# CTRL_V5.net
KiCad netlist of a schematic drawn in Altium Designer
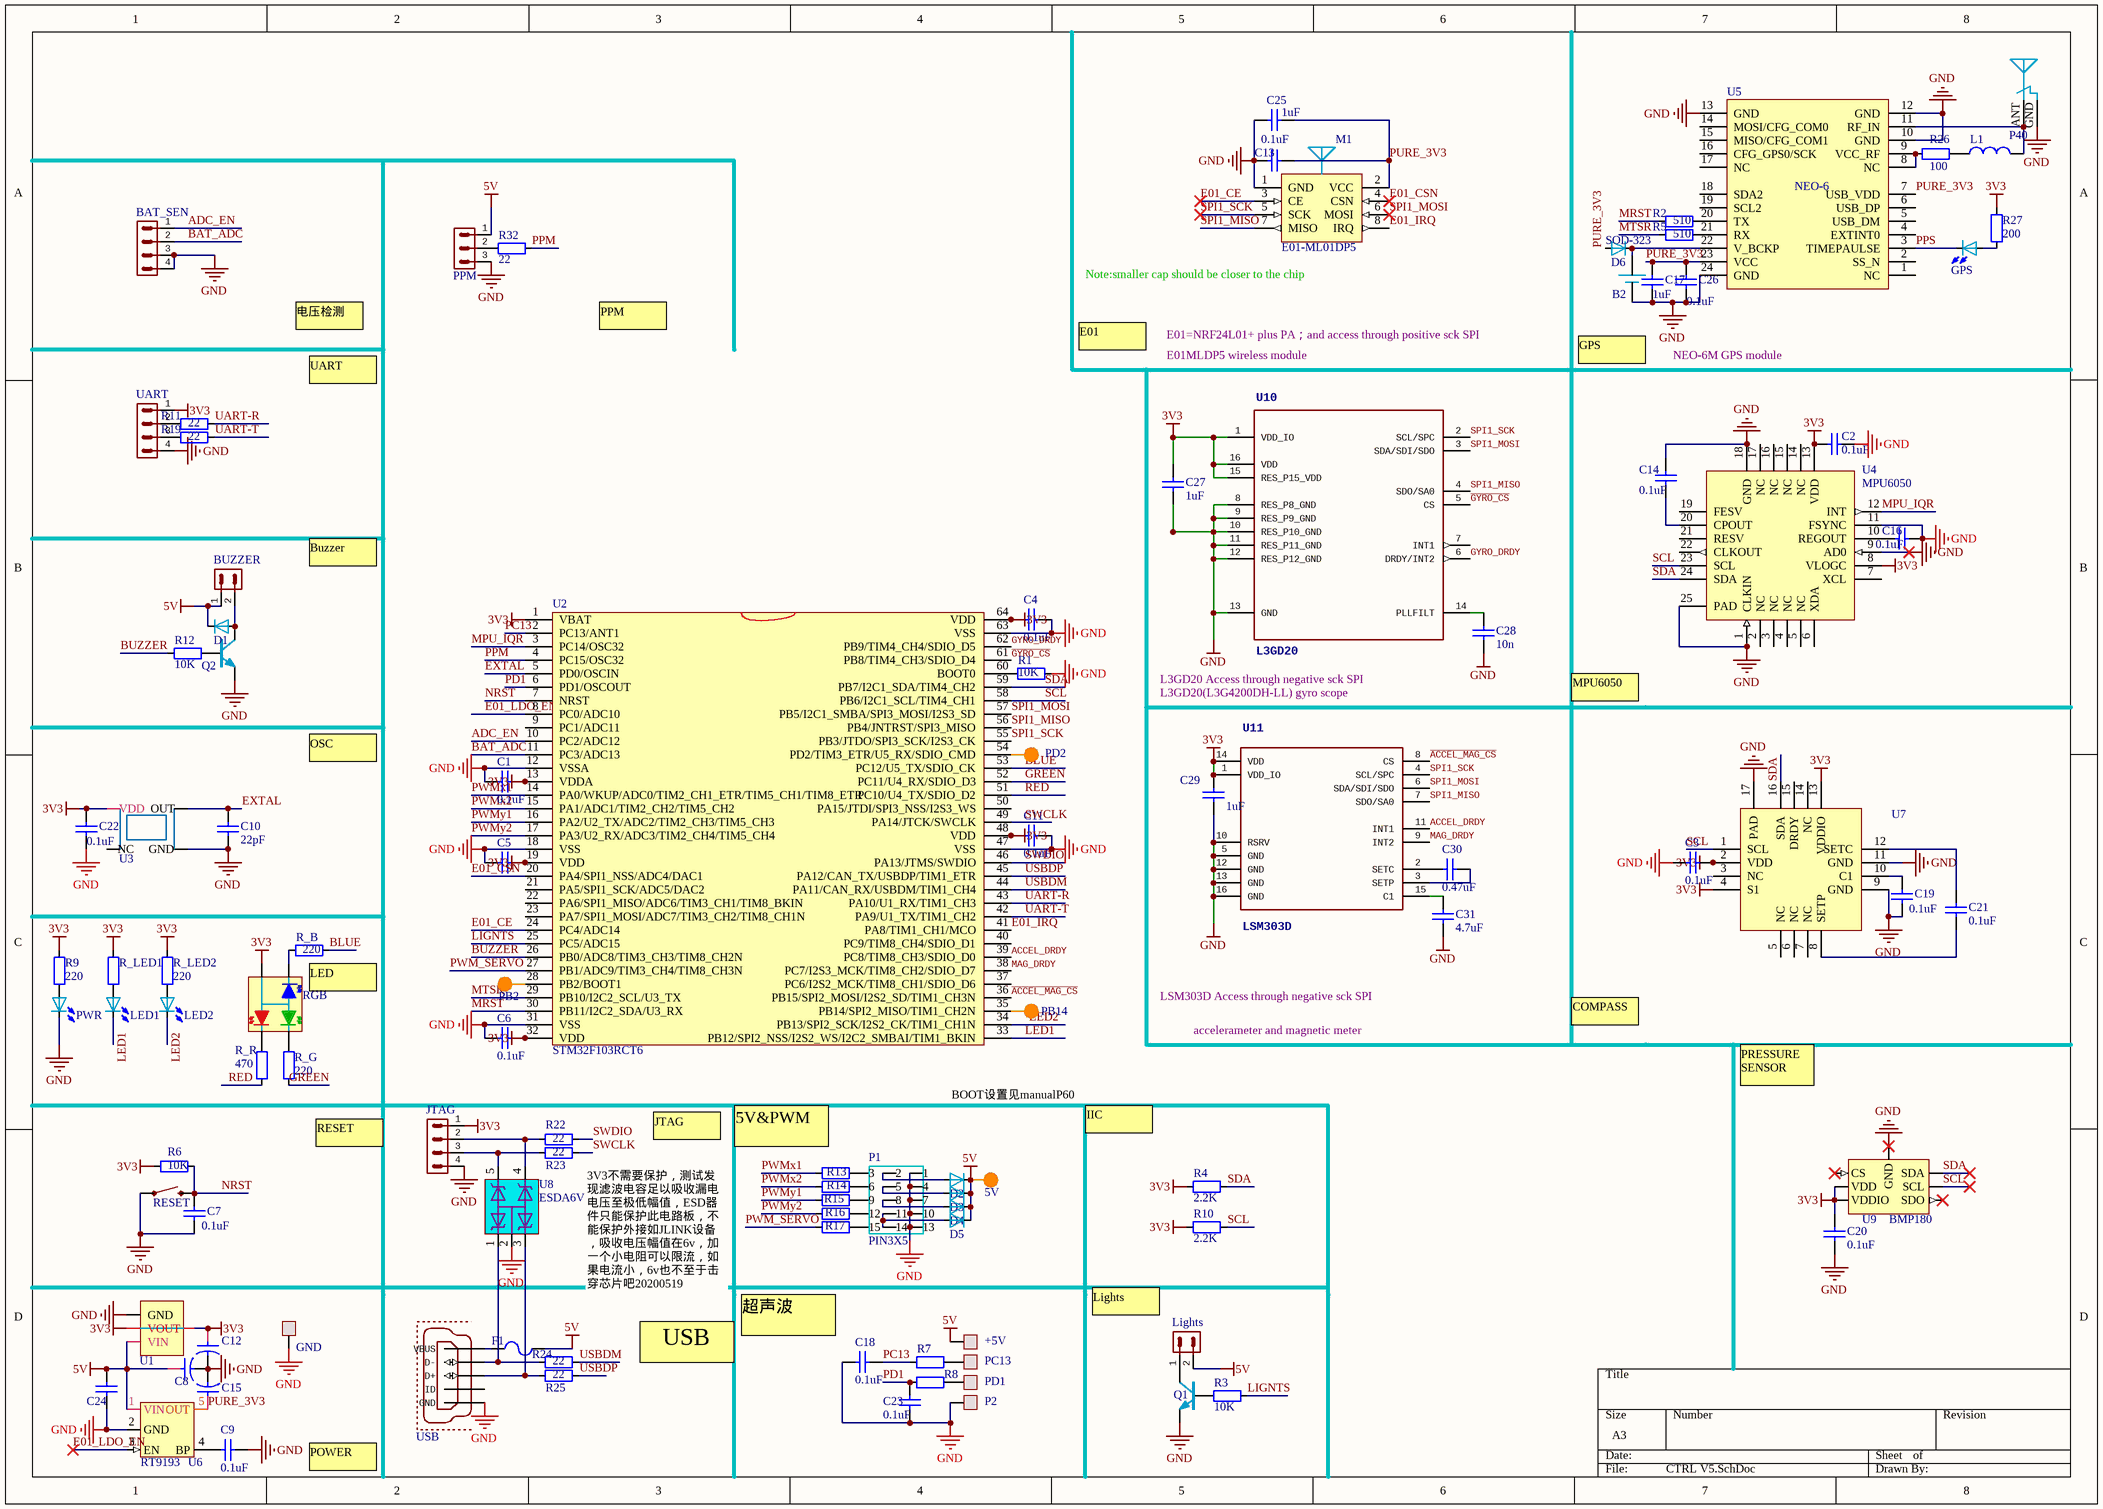
[diagram p0: CTRL V5.SchDoc]

(export (version "E")
  (design (tool "Eeschema 10.0.6"))
  (components
    (comp (ref "+5V") (value "voltage") (footprint "PIN1*1") (libsource (lib "") (part "PIN HDR 1x1_1")))
    (comp (ref "5V")
      (value "voltage")
      (footprint "TEST_P")
      (description "信号测试点")
      (libsource (lib "My_Library") (part "TEST"))
    )
    (comp (ref "B2")
      (value "XH414")
      (footprint "XH414")
      (description "XH414贴片法拉电容φ4.7")
      (libsource (lib "My_Library") (part "XH414"))
    )
    (comp (ref "BAT_SEN")
      (value "DF13C-4P")
      (footprint "DF13C-4P-1.25V")
      (description "1x4-Pin-connector")
      (fields (field (name "PUBLISHER") "Altium Limited"))
      (libsource (lib "My_Library") (part "PIN HDR 1x4"))
    )
    (comp (ref "BUZZER")
      (value "DF13C-2P")
      (footprint "DF13C-2P-1.25V")
      (description "DF13C-2PHeader, 2-Pin")
      (fields (field (name "PUBLISHER") "Altium Limited"))
      (libsource (lib "My_Library") (part "PIN HDR 1x2"))
    )
    (comp (ref "C1")
      (value "0.1uF")
      (footprint "0603-CAP")
      (description "无极性Cap")
      (fields (field (name "VOLTAGE") "50V") (field (name "PUBLISHER") "Altium Limited"))
      (libsource (lib "My_Library") (part "Cap"))
    )
    (comp (ref "C2")
      (value "0.1uF")
      (footprint "0603-CAP")
      (description "无极性Cap")
      (fields (field (name "VOLTAGE") "50V") (field (name "PUBLISHER") "Altium Limited"))
      (libsource (lib "My_Library") (part "Cap"))
    )
    (comp (ref "C3")
      (value "0.1uF")
      (footprint "0603-CAP")
      (description "无极性Cap")
      (fields (field (name "VOLTAGE") "50V") (field (name "PUBLISHER") "Altium Limited"))
      (libsource (lib "My_Library") (part "Cap"))
    )
    (comp (ref "C4")
      (value "0.1uF")
      (footprint "0603-CAP")
      (description "无极性Cap")
      (fields (field (name "VOLTAGE") "50V") (field (name "PUBLISHER") "Altium Limited"))
      (libsource (lib "My_Library") (part "Cap"))
    )
    (comp (ref "C5")
      (value "0.1uF")
      (footprint "0603-CAP")
      (description "无极性Cap")
      (fields (field (name "VOLTAGE") "50V") (field (name "PUBLISHER") "Altium Limited"))
      (libsource (lib "My_Library") (part "Cap"))
    )
    (comp (ref "C6")
      (value "0.1uF")
      (footprint "0603-CAP")
      (description "无极性Cap")
      (fields (field (name "VOLTAGE") "50V") (field (name "PUBLISHER") "Altium Limited"))
      (libsource (lib "My_Library") (part "Cap"))
    )
    (comp (ref "C7")
      (value "0.1uF")
      (footprint "0603-CAP")
      (description "无极性Cap")
      (fields (field (name "VOLTAGE") "50V") (field (name "PUBLISHER") "Altium Limited"))
      (libsource (lib "My_Library") (part "Cap"))
    )
    (comp (ref "C8")
      (value "10uF")
      (footprint "TAJ-A(1206)[3216]")
      (description "有极性Cap")
      (libsource (lib "") (part "Cap_p_1"))
    )
    (comp (ref "C9")
      (value "0.1uF")
      (footprint "0603-CAP")
      (description "无极性Cap")
      (fields (field (name "VOLTAGE") "50V") (field (name "PUBLISHER") "Altium Limited"))
      (libsource (lib "My_Library") (part "Cap"))
    )
    (comp (ref "C10")
      (value "22pF")
      (footprint "0603-CAP")
      (description "无极性Cap")
      (fields (field (name "VOLTAGE") "50V") (field (name "PUBLISHER") "Altium Limited"))
      (libsource (lib "My_Library") (part "Cap"))
    )
    (comp (ref "C11")
      (value "0.1uF")
      (footprint "0603-CAP")
      (description "无极性Cap")
      (fields (field (name "VOLTAGE") "50V") (field (name "PUBLISHER") "Altium Limited"))
      (libsource (lib "My_Library") (part "Cap"))
    )
    (comp (ref "C12")
      (value "10uF")
      (footprint "TAJ-A(1206)[3216]")
      (description "有极性Cap")
      (libsource (lib "My_Library") (part "Cap_p"))
    )
    (comp (ref "C13")
      (value "0.1uF")
      (footprint "0603-CAP")
      (description "无极性Cap")
      (fields (field (name "VOLTAGE") "50V") (field (name "PUBLISHER") "Altium Limited"))
      (libsource (lib "My_Library") (part "Cap"))
    )
    (comp (ref "C14")
      (value "0.1uF")
      (footprint "0603-CAP")
      (description "无极性Cap")
      (fields (field (name "VOLTAGE") "50V") (field (name "PUBLISHER") "Altium Limited"))
      (libsource (lib "My_Library") (part "Cap"))
    )
    (comp (ref "C15")
      (value "10uF")
      (footprint "TAJ-A(1206)[3216]")
      (description "有极性Cap")
      (libsource (lib "My_Library") (part "Cap_p"))
    )
    (comp (ref "C16")
      (value "0.1uF")
      (footprint "0603-CAP")
      (description "无极性Cap")
      (fields (field (name "VOLTAGE") "50V") (field (name "PUBLISHER") "Altium Limited"))
      (libsource (lib "My_Library") (part "Cap"))
    )
    (comp (ref "C17")
      (value "1uF")
      (footprint "0805-CAP")
      (description "无极性Cap")
      (fields (field (name "VOLTAGE") "50V") (field (name "PUBLISHER") "Altium Limited"))
      (libsource (lib "My_Library") (part "Cap"))
    )
    (comp (ref "C18")
      (value "0.1uF")
      (footprint "0603-CAP")
      (description "无极性Cap")
      (fields (field (name "VOLTAGE") "50V") (field (name "PUBLISHER") "Altium Limited"))
      (libsource (lib "My_Library") (part "Cap"))
    )
    (comp (ref "C19")
      (value "0.1uF")
      (footprint "0603-CAP")
      (description "无极性Cap")
      (fields (field (name "VOLTAGE") "50V") (field (name "PUBLISHER") "Altium Limited"))
      (libsource (lib "My_Library") (part "Cap"))
    )
    (comp (ref "C20")
      (value "0.1uF")
      (footprint "0603-CAP")
      (description "无极性Cap")
      (fields (field (name "VOLTAGE") "50V") (field (name "PUBLISHER") "Altium Limited"))
      (libsource (lib "My_Library") (part "Cap"))
    )
    (comp (ref "C21")
      (value "0.1uF")
      (footprint "0603-CAP")
      (description "无极性Cap")
      (fields (field (name "VOLTAGE") "50V") (field (name "PUBLISHER") "Altium Limited"))
      (libsource (lib "My_Library") (part "Cap"))
    )
    (comp (ref "C22")
      (value "0.1uF")
      (footprint "0603-CAP")
      (description "无极性Cap")
      (fields (field (name "VOLTAGE") "50V") (field (name "PUBLISHER") "Altium Limited"))
      (libsource (lib "My_Library") (part "Cap"))
    )
    (comp (ref "C23")
      (value "0.1uF")
      (footprint "0603-CAP")
      (description "无极性Cap")
      (fields (field (name "VOLTAGE") "50V") (field (name "PUBLISHER") "Altium Limited"))
      (libsource (lib "My_Library") (part "Cap"))
    )
    (comp (ref "C24")
      (value "0.1uF")
      (footprint "0805-CAP")
      (description "无极性Cap")
      (fields (field (name "VOLTAGE") "50V") (field (name "PUBLISHER") "Altium Limited"))
      (libsource (lib "My_Library") (part "Cap"))
    )
    (comp (ref "C25")
      (value "1uF")
      (footprint "0805-CAP")
      (description "无极性Cap")
      (fields (field (name "VOLTAGE") "50V") (field (name "PUBLISHER") "Altium Limited"))
      (libsource (lib "My_Library") (part "Cap"))
    )
    (comp (ref "C26")
      (value "0.1uF")
      (footprint "0603-CAP")
      (description "无极性Cap")
      (fields (field (name "VOLTAGE") "50V") (field (name "PUBLISHER") "Altium Limited"))
      (libsource (lib "My_Library") (part "Cap"))
    )
    (comp (ref "C27")
      (value "1uF")
      (footprint "0805-CAP")
      (description "无极性Cap")
      (fields (field (name "VOLTAGE") "50V") (field (name "PUBLISHER") "Altium Limited"))
      (libsource (lib "My_Library") (part "Cap"))
    )
    (comp (ref "C28")
      (value "10n")
      (footprint "0603-CAP")
      (description "无极性Cap")
      (fields (field (name "VOLTAGE") "50V") (field (name "PUBLISHER") "Altium Limited"))
      (libsource (lib "My_Library") (part "Cap"))
    )
    (comp (ref "C29")
      (value "1uF")
      (footprint "0805-CAP")
      (description "无极性Cap")
      (fields (field (name "VOLTAGE") "50V") (field (name "PUBLISHER") "Altium Limited"))
      (libsource (lib "My_Library") (part "Cap"))
    )
    (comp (ref "C30")
      (value "0.47uF")
      (footprint "0603-CAP")
      (description "无极性Cap")
      (fields (field (name "VOLTAGE") "50V") (field (name "PUBLISHER") "Altium Limited"))
      (libsource (lib "My_Library") (part "Cap"))
    )
    (comp (ref "C31")
      (value "4.7uF")
      (footprint "0805-CAP")
      (description "无极性Cap")
      (fields (field (name "VOLTAGE") "50V") (field (name "PUBLISHER") "Altium Limited"))
      (libsource (lib "My_Library") (part "Cap"))
    )
    (comp (ref "D1")
      (value "shotechy")
      (footprint "SOD-323")
      (description "Diode")
      (libsource (lib "My_Library") (part "DIODE"))
    )
    (comp (ref "D2")
      (value "1N4148")
      (footprint "SOD-523")
      (description "Diode")
      (libsource (lib "My_Library") (part "DIODE"))
    )
    (comp (ref "D3")
      (value "1N4148")
      (footprint "SOD-523")
      (description "Diode")
      (libsource (lib "My_Library") (part "DIODE"))
    )
    (comp (ref "D4")
      (value "1N4148")
      (footprint "SOD-523")
      (description "Diode")
      (libsource (lib "My_Library") (part "DIODE"))
    )
    (comp (ref "D5")
      (value "1N4148")
      (footprint "SOD-523")
      (description "Diode")
      (libsource (lib "My_Library") (part "DIODE"))
    )
    (comp (ref "D6")
      (value "SOD-323")
      (footprint "SOD-323")
      (description "Diode")
      (libsource (lib "My_Library") (part "DIODE"))
    )
    (comp (ref "F1")
      (value "FUSE")
      (footprint "0805-FUS")
      (description "熔断器")
      (libsource (lib "My_Library") (part "FUSE"))
    )
    (comp (ref "GND")
      (value "voltage")
      (footprint "PIN1*1")
      (libsource (lib "My_Library") (part "PIN HDR 1x1"))
    )
    (comp (ref "GPS") (value "LED") (footprint "0805-LED") (libsource (lib "My_Library") (part "LED")))
    (comp (ref "JTAG")
      (value "PIN HDR 1x4")
      (footprint "PIN4*1")
      (description "1x4-Pin-connector-JTAG")
      (fields (field (name "PUBLISHER") "Altium Limited"))
      (libsource (lib "My_Library") (part "PIN HDR 1x4"))
    )
    (comp (ref "L1")
      (value "value")
      (footprint "0805-IND")
      (description "电感")
      (libsource (lib "My_Library") (part "Inductor"))
    )
    (comp (ref "LED1") (value "LED") (footprint "0805-LED") (libsource (lib "My_Library") (part "LED")))
    (comp (ref "LED2") (value "LED") (footprint "0805-LED") (libsource (lib "My_Library") (part "LED")))
    (comp (ref "Lights")
      (value "DF13C-2P")
      (footprint "DF13C-2P-1.25V")
      (description "Header, 2-Pin")
      (fields (field (name "PUBLISHER") "Altium Limited"))
      (libsource (lib "My_Library") (part "PIN HDR 1x2"))
    )
    (comp (ref "M1")
      (value "E01-ML01DP5")
      (footprint "E01-ML01DP5 - SMD")
      (description "无线模块E01-ML01DP5")
      (libsource (lib "My_Library") (part "E01-ML01DP5"))
    )
    (comp (ref "P1")
      (value "PIN3X5")
      (footprint "PIN HDR3X5")
      (libsource (lib "My_Library") (part "PIN HDR3x5"))
    )
    (comp (ref "P2") (value "voltage") (footprint "PIN1*1") (libsource (lib "") (part "PIN HDR 1x1_1")))
    (comp (ref "P40")
      (value "IPEX")
      (footprint "IPEX")
      (description "IPEX天线座")
      (libsource (lib "My_Library") (part "IPEX"))
    )
    (comp (ref "PB2")
      (value "voltage")
      (footprint "TEST_P")
      (description "信号测试点")
      (libsource (lib "My_Library") (part "TEST"))
    )
    (comp (ref "PB14")
      (value "voltage")
      (footprint "TEST_P")
      (description "信号测试点")
      (libsource (lib "My_Library") (part "TEST"))
    )
    (comp (ref "PC13") (value "voltage") (footprint "PIN1*1") (libsource (lib "") (part "PIN HDR 1x1_1")))
    (comp (ref "PD1") (value "voltage") (footprint "PIN1*1") (libsource (lib "") (part "PIN HDR 1x1_1")))
    (comp (ref "PD2")
      (value "voltage")
      (footprint "TEST_P")
      (description "信号测试点")
      (libsource (lib "My_Library") (part "TEST"))
    )
    (comp (ref "PPM")
      (value "PIN HDR 1X3")
      (footprint "PIN3*1")
      (libsource (lib "My_Library") (part "PIN HDR 1X3"))
    )
    (comp (ref "PWR") (value "LED") (footprint "0805-LED") (libsource (lib "My_Library") (part "LED")))
    (comp (ref "Q1")
      (value "2N3904")
      (footprint "SOT-23")
      (description "NPN三极管")
      (libsource (lib "") (part "NPN_1"))
    )
    (comp (ref "Q2")
      (value "2N3904")
      (footprint "SOT-23")
      (description "NPN三极管")
      (libsource (lib "My_Library") (part "NPN"))
    )
    (comp (ref "R1")
      (value "10K")
      (footprint "0603-Res")
      (description "Resistor")
      (fields (field (name "PUBLISHER") "Altium Limited"))
      (libsource (lib "My_Library") (part "RES"))
    )
    (comp (ref "R2")
      (value "510")
      (footprint "0603-Res")
      (description "Resistor")
      (fields (field (name "PUBLISHER") "Altium Limited"))
      (libsource (lib "") (part "RES_1"))
    )
    (comp (ref "R3")
      (value "10K")
      (footprint "0603-Res")
      (description "Resistor")
      (fields (field (name "PUBLISHER") "Altium Limited"))
      (libsource (lib "") (part "RES_2"))
    )
    (comp (ref "R4")
      (value "2.2K")
      (footprint "0603-Res")
      (description "Resistor")
      (fields (field (name "PUBLISHER") "Altium Limited"))
      (libsource (lib "My_Library") (part "RES"))
    )
    (comp (ref "R5")
      (value "510")
      (footprint "0603-Res")
      (description "Resistor")
      (fields (field (name "PUBLISHER") "Altium Limited"))
      (libsource (lib "") (part "RES_1"))
    )
    (comp (ref "R6")
      (value "10K")
      (footprint "0603-Res")
      (description "Resistor")
      (fields (field (name "PUBLISHER") "Altium Limited"))
      (libsource (lib "") (part "RES_1"))
    )
    (comp (ref "R7")
      (value "220")
      (footprint "0603-Res")
      (description "Resistor")
      (fields (field (name "PUBLISHER") "Altium Limited"))
      (libsource (lib "") (part "RES_1"))
    )
    (comp (ref "R8")
      (value "220")
      (footprint "0603-Res")
      (description "Resistor")
      (fields (field (name "PUBLISHER") "Altium Limited"))
      (libsource (lib "") (part "RES_1"))
    )
    (comp (ref "R9")
      (value "220")
      (footprint "0603-Res")
      (description "Resistor")
      (fields (field (name "PUBLISHER") "Altium Limited"))
      (libsource (lib "My_Library") (part "RES"))
    )
    (comp (ref "R10")
      (value "2.2K")
      (footprint "0603-Res")
      (description "Resistor")
      (fields (field (name "PUBLISHER") "Altium Limited"))
      (libsource (lib "My_Library") (part "RES"))
    )
    (comp (ref "R11")
      (value "22")
      (footprint "0603-Res")
      (description "Resistor")
      (fields (field (name "PUBLISHER") "Altium Limited"))
      (libsource (lib "") (part "RES_3"))
    )
    (comp (ref "R12")
      (value "10K")
      (footprint "0603-Res")
      (description "Resistor")
      (fields (field (name "PUBLISHER") "Altium Limited"))
      (libsource (lib "My_Library") (part "RES"))
    )
    (comp (ref "R13")
      (value "220")
      (footprint "0603-Res")
      (description "Resistor")
      (fields (field (name "PUBLISHER") "Altium Limited"))
      (libsource (lib "My_Library") (part "RES"))
    )
    (comp (ref "R14")
      (value "220")
      (footprint "0603-Res")
      (description "Resistor")
      (fields (field (name "PUBLISHER") "Altium Limited"))
      (libsource (lib "My_Library") (part "RES"))
    )
    (comp (ref "R15")
      (value "220")
      (footprint "0603-Res")
      (description "Resistor")
      (fields (field (name "PUBLISHER") "Altium Limited"))
      (libsource (lib "My_Library") (part "RES"))
    )
    (comp (ref "R16")
      (value "220")
      (footprint "0603-Res")
      (description "Resistor")
      (fields (field (name "PUBLISHER") "Altium Limited"))
      (libsource (lib "My_Library") (part "RES"))
    )
    (comp (ref "R17")
      (value "220")
      (footprint "0603-Res")
      (description "Resistor")
      (fields (field (name "PUBLISHER") "Altium Limited"))
      (libsource (lib "My_Library") (part "RES"))
    )
    (comp (ref "R19")
      (value "22")
      (footprint "0603-Res")
      (description "Resistor")
      (fields (field (name "PUBLISHER") "Altium Limited"))
      (libsource (lib "") (part "RES_3"))
    )
    (comp (ref "R22")
      (value "22")
      (footprint "0603-Res")
      (description "Resistor")
      (fields (field (name "PUBLISHER") "Altium Limited"))
      (libsource (lib "") (part "RES_3"))
    )
    (comp (ref "R23")
      (value "22")
      (footprint "0603-Res")
      (description "Resistor")
      (fields (field (name "PUBLISHER") "Altium Limited"))
      (libsource (lib "") (part "RES_3"))
    )
    (comp (ref "R24")
      (value "22")
      (footprint "0603-Res")
      (description "Resistor")
      (fields (field (name "PUBLISHER") "Altium Limited"))
      (libsource (lib "") (part "RES_1"))
    )
    (comp (ref "R25")
      (value "22")
      (footprint "0603-Res")
      (description "Resistor")
      (fields (field (name "PUBLISHER") "Altium Limited"))
      (libsource (lib "") (part "RES_1"))
    )
    (comp (ref "R26")
      (value "100")
      (footprint "0603-Res")
      (description "Resistor")
      (fields (field (name "PUBLISHER") "Altium Limited"))
      (libsource (lib "") (part "RES_1"))
    )
    (comp (ref "R27")
      (value "200")
      (footprint "0603-Res")
      (description "Resistor")
      (fields (field (name "PUBLISHER") "Altium Limited"))
      (libsource (lib "") (part "RES_3"))
    )
    (comp (ref "R32")
      (value "22")
      (footprint "0603-Res")
      (description "Resistor")
      (fields (field (name "PUBLISHER") "Altium Limited"))
      (libsource (lib "") (part "RES_2"))
    )
    (comp (ref "RESET")
      (value "KEY_2PIN")
      (footprint "KEY-SMD-2P-1")
      (libsource (lib "My_Library") (part "KEY_2PIN"))
    )
    (comp (ref "RGB")
      (value "3528LED")
      (footprint "1210-RGBLED")
      (libsource (lib "My_Library") (part "LED-RGB-4PIN"))
    )
    (comp (ref "R_B")
      (value "220")
      (footprint "0603-Res")
      (description "Resistor")
      (fields (field (name "PUBLISHER") "Altium Limited"))
      (libsource (lib "") (part "RES_3"))
    )
    (comp (ref "R_G")
      (value "220")
      (footprint "0603-Res")
      (description "Resistor")
      (fields (field (name "PUBLISHER") "Altium Limited"))
      (libsource (lib "My_Library") (part "RES"))
    )
    (comp (ref "R_LED1")
      (value "220")
      (footprint "0603-Res")
      (description "Resistor")
      (fields (field (name "PUBLISHER") "Altium Limited"))
      (libsource (lib "My_Library") (part "RES"))
    )
    (comp (ref "R_LED2")
      (value "220")
      (footprint "0603-Res")
      (description "Resistor")
      (fields (field (name "PUBLISHER") "Altium Limited"))
      (libsource (lib "My_Library") (part "RES"))
    )
    (comp (ref "R_R")
      (value "470")
      (footprint "0603-Res")
      (description "Resistor")
      (fields (field (name "PUBLISHER") "Altium Limited"))
      (libsource (lib "My_Library") (part "RES"))
    )
    (comp (ref "U1")
      (value "AMS1117-3.3")
      (footprint "SOT-223")
      (libsource (lib "My_Library") (part "AMS1117"))
    )
    (comp (ref "U2")
      (value "STM32F103RCT6")
      (footprint "LQFP-64-S")
      (libsource (lib "My_Library") (part "STM32F103RCT6"))
    )
    (comp (ref "U3")
      (value "5032-8M")
      (footprint "XTAL-5032-4P")
      (description "4PIN-5032晶振")
      (libsource (lib "My_Library") (part "XTAL-5032-4P"))
    )
    (comp (ref "U4")
      (value "MPU6050")
      (footprint "QFN-24")
      (description "dscrps三轴陀螺仪加速度计")
      (libsource (lib "My_Library") (part "MPU6050"))
    )
    (comp (ref "U5")
      (value "NEO-6")
      (footprint "NEO-6")
      (description "GPS")
      (libsource (lib "My_Library") (part "NEO-6"))
    )
    (comp (ref "U6") (value "RT9193") (footprint "SOT23-5") (libsource (lib "My_Library") (part "RT9193")))
    (comp (ref "U7")
      (value "HMC5883")
      (footprint "QFN-16-L")
      (description "地磁计")
      (libsource (lib "My_Library") (part "HMC5883"))
    )
    (comp (ref "U8")
      (value "ESDA6V1W5(Eb1)")
      (footprint "SOT323-5L")
      (description "ESD protection")
      (libsource (lib "My_Library") (part "ESDA6V1W5(Eb1)"))
    )
    (comp (ref "U9")
      (value "BMP180")
      (footprint "BMP180-WITHSHELL")
      (description "Special BOSCH pressure sensor")
      (libsource (lib "My_Library") (part "BMP180"))
    )
    (comp (ref "U10")
      (value "L3GD20")
      (footprint "L3G4200DH-MAN")
      (libsource (lib "pixhawk2") (part "L3G4200DH-LL"))
    )
    (comp (ref "U11") (value "LSM303D") (footprint "LGA-16L") (libsource (lib "pixhawk2") (part "LSM303D")))
    (comp (ref "UART")
      (value "SH1.0-4P")
      (footprint "SH1.0 S-W-4P")
      (description "SH1.0-4P 1x4-Pin-connector")
      (fields (field (name "PUBLISHER") "Altium Limited"))
      (libsource (lib "My_Library") (part "PIN HDR 1x4"))
    )
    (comp (ref "USB")
      (value "USB-MICRO")
      (footprint "USB_MICRO")
      (description "USB")
      (libsource (lib "My_Library") (part "USB"))
    )
  )
  (nets
    (net (code "1") (name "/ACCEL_DRDY") (class "Default")
      (node (ref "U11") (pin "11") (pinfunction "INT1_11") (pintype "passive"))
      (node (ref "U2") (pin "39") (pinfunction "PC8/TIM8_CH3/SDIO_D0_39") (pintype "passive"))
    )
    (net (code "2") (name "/ADC_EN") (class "Default")
      (node (ref "BAT_SEN") (pin "1") (pinfunction "1_1") (pintype "passive"))
      (node (ref "U2") (pin "10") (pinfunction "PC2/ADC12_10") (pintype "passive"))
    )
    (net (code "3") (name "/BAT_ADC") (class "Default")
      (node (ref "BAT_SEN") (pin "2") (pinfunction "2_2") (pintype "passive"))
      (node (ref "U2") (pin "11") (pinfunction "PC3/ADC13_11") (pintype "passive"))
    )
    (net (code "4") (name "/BLUE") (class "Default")
      (node (ref "R_B") (pin "2") (pinfunction "2_2") (pintype "passive"))
      (node (ref "U2") (pin "53") (pinfunction "PC12/U5_TX/SDIO_CK_53") (pintype "passive"))
    )
    (net (code "5") (name "/BUZZER") (class "Default")
      (node (ref "R12") (pin "2") (pinfunction "2_2") (pintype "passive"))
      (node (ref "U2") (pin "26") (pinfunction "PB0/ADC8/TIM3_CH3/TIM8_CH2N_26") (pintype "passive"))
    )
    (net (code "6") (name "/E01_CE") (class "Default")
      (node (ref "M1") (pin "3") (pinfunction "CE_3") (pintype "input"))
      (node (ref "U2") (pin "24") (pinfunction "PC4/ADC14_24") (pintype "passive"))
    )
    (net (code "7") (name "/E01_CSN") (class "Default")
      (node (ref "M1") (pin "4") (pinfunction "CSN_4") (pintype "input"))
      (node (ref "U2") (pin "20") (pinfunction "PA4/SPI1_NSS/ADC4/DAC1_20") (pintype "passive"))
    )
    (net (code "8") (name "/E01_IRQ") (class "Default")
      (node (ref "M1") (pin "8") (pinfunction "IRQ_8") (pintype "output"))
      (node (ref "U2") (pin "41") (pinfunction "PA8/TIM1_CH1/MCO_41") (pintype "passive"))
    )
    (net (code "9") (name "/E01_LDO_EN") (class "Default")
      (node (ref "U2") (pin "8") (pinfunction "PC0/ADC10_8") (pintype "passive"))
      (node (ref "U6") (pin "3") (pinfunction "EN_3") (pintype "input"))
    )
    (net (code "10") (name "/EXTAL") (class "Default")
      (node (ref "C10") (pin "2") (pinfunction "2_2") (pintype "passive"))
      (node (ref "U2") (pin "5") (pinfunction "PD0/OSCIN_5") (pintype "passive"))
      (node (ref "U3") (pin "3") (pinfunction "OUT_3") (pintype "passive"))
    )
    (net (code "11") (name "/GREEN") (class "Default")
      (node (ref "R_G") (pin "2") (pinfunction "2_2") (pintype "passive"))
      (node (ref "U2") (pin "52") (pinfunction "PC11/U4_RX/SDIO_D3_52") (pintype "passive"))
    )
    (net (code "12") (name "/GYRO_DRDY") (class "Default")
      (node (ref "U10") (pin "6") (pinfunction "DRDY/INT2_6") (pintype "output"))
      (node (ref "U2") (pin "62") (pinfunction "PB9/TIM4_CH4/SDIO_D5_62") (pintype "passive"))
    )
    (net (code "13") (name "/LED1") (class "Default")
      (node (ref "LED1") (pin "C") (pinfunction "2_C") (pintype "passive"))
      (node (ref "U2") (pin "33") (pinfunction "PB12/SPI2_NSS/I2S2_WS/I2C2_SMBAI/TIM1_BKIN_33") (pintype "passive"))
    )
    (net (code "14") (name "/LED2") (class "Default")
      (node (ref "LED2") (pin "C") (pinfunction "2_C") (pintype "passive"))
      (node (ref "U2") (pin "34") (pinfunction "PB13/SPI2_SCK/I2S2_CK/TIM1_CH1N_34") (pintype "passive"))
    )
    (net (code "15") (name "/LIGNTS") (class "Default")
      (node (ref "R3") (pin "1") (pinfunction "1_1") (pintype "passive"))
      (node (ref "U2") (pin "25") (pinfunction "PC5/ADC15_25") (pintype "passive"))
    )
    (net (code "16") (name "/MAG_DRDY") (class "Default")
      (node (ref "U11") (pin "9") (pinfunction "INT2_9") (pintype "passive"))
      (node (ref "U2") (pin "38") (pinfunction "PC7/I2S3_MCK/TIM8_CH2/SDIO_D7_38") (pintype "passive"))
    )
    (net (code "17") (name "/MPU_IQR") (class "Default")
      (node (ref "U2") (pin "3") (pinfunction "PC14/OSC32_3") (pintype "passive"))
      (node (ref "U4") (pin "12") (pinfunction "INT_12") (pintype "output"))
    )
    (net (code "18") (name "/MRST") (class "Default")
      (node (ref "R2") (pin "1") (pinfunction "1_1") (pintype "passive"))
      (node (ref "U2") (pin "30") (pinfunction "PB11/I2C2_SDA/U3_RX_30") (pintype "passive"))
    )
    (net (code "19") (name "/MTSR") (class "Default")
      (node (ref "R5") (pin "1") (pinfunction "1_1") (pintype "passive"))
      (node (ref "U2") (pin "29") (pinfunction "PB10/I2C2_SCL/U3_TX_29") (pintype "passive"))
    )
    (net (code "20") (name "/NRST") (class "Default")
      (node (ref "C7") (pin "2") (pinfunction "2_2") (pintype "passive"))
      (node (ref "R6") (pin "2") (pinfunction "2_2") (pintype "passive"))
      (node (ref "RESET") (pin "2") (pinfunction "2_2") (pintype "passive"))
      (node (ref "U2") (pin "7") (pinfunction "NRST_7") (pintype "passive"))
    )
    (net (code "21") (name "/PC13") (class "Default")
      (node (ref "C18") (pin "2") (pinfunction "2_2") (pintype "passive"))
      (node (ref "R7") (pin "1") (pinfunction "1_1") (pintype "passive"))
      (node (ref "U2") (pin "2") (pinfunction "PC13/ANT1_2") (pintype "passive"))
    )
    (net (code "22") (name "/PD1") (class "Default")
      (node (ref "C23") (pin "2") (pinfunction "2_2") (pintype "passive"))
      (node (ref "R8") (pin "1") (pinfunction "1_1") (pintype "passive"))
      (node (ref "U2") (pin "6") (pinfunction "PD1/OSCOUT_6") (pintype "passive"))
    )
    (net (code "23") (name "/PPM") (class "Default")
      (node (ref "R32") (pin "1") (pinfunction "1_1") (pintype "passive"))
      (node (ref "U2") (pin "4") (pinfunction "PC15/OSC32_4") (pintype "passive"))
    )
    (net (code "24") (name "/PPS") (class "Default")
      (node (ref "GPS") (pin "C") (pinfunction "2_C") (pintype "passive"))
      (node (ref "U5") (pin "3") (pinfunction "TIMEPAULSE_3") (pintype "passive"))
    )
    (net (code "25") (name "/PURE_3V3") (class "Default")
      (node (ref "C13") (pin "2") (pinfunction "2_2") (pintype "passive"))
      (node (ref "C15") (pin "A") (pinfunction "A_A") (pintype "passive"))
      (node (ref "C17") (pin "2") (pinfunction "2_2") (pintype "passive"))
      (node (ref "C25") (pin "1") (pinfunction "1_1") (pintype "passive"))
      (node (ref "C26") (pin "2") (pinfunction "2_2") (pintype "passive"))
      (node (ref "D6") (pin "A") (pinfunction "1_A") (pintype "passive"))
      (node (ref "M1") (pin "2") (pinfunction "VCC_2") (pintype "power_in"))
      (node (ref "U5") (pin "23") (pinfunction "VCC_23") (pintype "passive"))
      (node (ref "U5") (pin "7") (pinfunction "USB_VDD_7") (pintype "passive"))
      (node (ref "U6") (pin "5") (pinfunction "OUT_5") (pintype "passive"))
    )
    (net (code "26") (name "/PWM_SERVO") (class "Default")
      (node (ref "R17") (pin "2") (pinfunction "2_2") (pintype "passive"))
      (node (ref "U2") (pin "27") (pinfunction "PB1/ADC9/TIM3_CH4/TIM8_CH3N_27") (pintype "passive"))
    )
    (net (code "27") (name "/PWMx1") (class "Default")
      (node (ref "R13") (pin "2") (pinfunction "2_2") (pintype "passive"))
      (node (ref "U2") (pin "14") (pinfunction "PA0/WKUP/ADC0/TIM2_CH1_ETR/TIM5_CH1/TIM8_ETR_14") (pintype "passive"))
    )
    (net (code "28") (name "/PWMx2") (class "Default")
      (node (ref "R14") (pin "2") (pinfunction "2_2") (pintype "passive"))
      (node (ref "U2") (pin "15") (pinfunction "PA1/ADC1/TIM2_CH2/TIM5_CH2_15") (pintype "passive"))
    )
    (net (code "29") (name "/PWMy1") (class "Default")
      (node (ref "R15") (pin "2") (pinfunction "2_2") (pintype "passive"))
      (node (ref "U2") (pin "16") (pinfunction "PA2/U2_TX/ADC2/TIM2_CH3/TIM5_CH3_16") (pintype "passive"))
    )
    (net (code "30") (name "/PWMy2") (class "Default")
      (node (ref "R16") (pin "2") (pinfunction "2_2") (pintype "passive"))
      (node (ref "U2") (pin "17") (pinfunction "PA3/U2_RX/ADC3/TIM2_CH4/TIM5_CH4_17") (pintype "passive"))
    )
    (net (code "31") (name "/RED") (class "Default")
      (node (ref "R_R") (pin "2") (pinfunction "2_2") (pintype "passive"))
      (node (ref "U2") (pin "51") (pinfunction "PC10/U4_TX/SDIO_D2_51") (pintype "passive"))
    )
    (net (code "32") (name "/SCL") (class "Default")
      (node (ref "R10") (pin "1") (pinfunction "1_1") (pintype "passive"))
      (node (ref "U2") (pin "58") (pinfunction "PB6/I2C1_SCL/TIM4_CH1_58") (pintype "passive"))
      (node (ref "U4") (pin "23") (pinfunction "SCL_23") (pintype "open_collector"))
      (node (ref "U7") (pin "1") (pinfunction "SCL_1") (pintype "passive"))
      (node (ref "U9") (pin "5") (pinfunction "SCL_5") (pintype "open_collector"))
    )
    (net (code "33") (name "/SDA") (class "Default")
      (node (ref "R4") (pin "1") (pinfunction "1_1") (pintype "passive"))
      (node (ref "U2") (pin "59") (pinfunction "PB7/I2C1_SDA/TIM4_CH2_59") (pintype "passive"))
      (node (ref "U4") (pin "24") (pinfunction "SDA_24") (pintype "open_collector"))
      (node (ref "U7") (pin "16") (pinfunction "SDA_16") (pintype "passive"))
      (node (ref "U9") (pin "6") (pinfunction "SDA_6") (pintype "open_collector"))
    )
    (net (code "34") (name "/SPI1_MISO") (class "Default")
      (node (ref "M1") (pin "7") (pinfunction "MISO_7") (pintype "output"))
      (node (ref "U10") (pin "4") (pinfunction "SDO/SA0_4") (pintype "passive"))
      (node (ref "U11") (pin "7") (pinfunction "SDO/SA0_7") (pintype "passive"))
      (node (ref "U2") (pin "56") (pinfunction "PB4/JNTRST/SPI3_MISO_56") (pintype "passive"))
    )
    (net (code "35") (name "/SPI1_MOSI") (class "Default")
      (node (ref "M1") (pin "6") (pinfunction "MOSI_6") (pintype "input"))
      (node (ref "U10") (pin "3") (pinfunction "SDA/SDI/SDO_3") (pintype "passive"))
      (node (ref "U11") (pin "6") (pinfunction "SDA/SDI/SDO_6") (pintype "passive"))
      (node (ref "U2") (pin "57") (pinfunction "PB5/I2C1_SMBA/SPI3_MOSI/I2S3_SD_57") (pintype "passive"))
    )
    (net (code "36") (name "/SPI1_SCK") (class "Default")
      (node (ref "M1") (pin "5") (pinfunction "SCK_5") (pintype "input"))
      (node (ref "U10") (pin "2") (pinfunction "SCL/SPC_2") (pintype "passive"))
      (node (ref "U11") (pin "4") (pinfunction "SCL/SPC_4") (pintype "passive"))
      (node (ref "U2") (pin "55") (pinfunction "PB3/JTDO/SPI3_SCK/I2S3_CK_55") (pintype "passive"))
    )
    (net (code "37") (name "/SWCLK") (class "Default")
      (node (ref "R23") (pin "2") (pinfunction "2_2") (pintype "passive"))
      (node (ref "U2") (pin "49") (pinfunction "PA14/JTCK/SWCLK_49") (pintype "passive"))
    )
    (net (code "38") (name "/SWDIO") (class "Default")
      (node (ref "R22") (pin "2") (pinfunction "2_2") (pintype "passive"))
      (node (ref "U2") (pin "46") (pinfunction "PA13/JTMS/SWDIO_46") (pintype "passive"))
    )
    (net (code "39") (name "/UART-R") (class "Default")
      (node (ref "R11") (pin "2") (pinfunction "2_2") (pintype "passive"))
      (node (ref "U2") (pin "43") (pinfunction "PA10/U1_RX/TIM1_CH3_43") (pintype "passive"))
    )
    (net (code "40") (name "/UART-T") (class "Default")
      (node (ref "R19") (pin "2") (pinfunction "2_2") (pintype "passive"))
      (node (ref "U2") (pin "42") (pinfunction "PA9/U1_TX/TIM1_CH2_42") (pintype "passive"))
    )
    (net (code "41") (name "/USBDM") (class "Default")
      (node (ref "R24") (pin "2") (pinfunction "2_2") (pintype "passive"))
      (node (ref "U2") (pin "44") (pinfunction "PA11/CAN_RX/USBDM/TIM1_CH4_44") (pintype "passive"))
    )
    (net (code "42") (name "/USBDP") (class "Default")
      (node (ref "R25") (pin "2") (pinfunction "2_2") (pintype "passive"))
      (node (ref "U2") (pin "45") (pinfunction "PA12/CAN_TX/USBDP/TIM1_ETR_45") (pintype "passive"))
    )
    (net (code "43") (name "/~{ACCEL_MAG_CS}") (class "Default")
      (node (ref "U11") (pin "8") (pinfunction "CS_8") (pintype "passive"))
      (node (ref "U2") (pin "36") (pinfunction "PB15/SPI2_MOSI/I2S2_SD/TIM1_CH3N_36") (pintype "passive"))
    )
    (net (code "44") (name "/~{GYRO_CS}") (class "Default")
      (node (ref "U10") (pin "5") (pinfunction "CS_5") (pintype "passive"))
      (node (ref "U2") (pin "61") (pinfunction "PB8/TIM4_CH3/SDIO_D4_61") (pintype "passive"))
    )
    (net (code "45") (name "3V3") (class "Default")
      (node (ref "C1") (pin "1") (pinfunction "1_1") (pintype "passive"))
      (node (ref "C11") (pin "2") (pinfunction "2_2") (pintype "passive"))
      (node (ref "C12") (pin "A") (pinfunction "A_A") (pintype "passive"))
      (node (ref "C2") (pin "1") (pinfunction "1_1") (pintype "passive"))
      (node (ref "C20") (pin "2") (pinfunction "2_2") (pintype "passive"))
      (node (ref "C22") (pin "2") (pinfunction "2_2") (pintype "passive"))
      (node (ref "C27") (pin "2") (pinfunction "2_2") (pintype "passive"))
      (node (ref "C29") (pin "2") (pinfunction "2_2") (pintype "passive"))
      (node (ref "C3") (pin "2") (pinfunction "2_2") (pintype "passive"))
      (node (ref "C4") (pin "2") (pinfunction "2_2") (pintype "passive"))
      (node (ref "C5") (pin "2") (pinfunction "2_2") (pintype "passive"))
      (node (ref "C6") (pin "1") (pinfunction "1_1") (pintype "passive"))
      (node (ref "JTAG") (pin "1") (pinfunction "1_1") (pintype "passive"))
      (node (ref "R10") (pin "2") (pinfunction "2_2") (pintype "passive"))
      (node (ref "R27") (pin "2") (pinfunction "2_2") (pintype "passive"))
      (node (ref "R4") (pin "2") (pinfunction "2_2") (pintype "passive"))
      (node (ref "R6") (pin "1") (pinfunction "1_1") (pintype "passive"))
      (node (ref "R9") (pin "1") (pinfunction "1_1") (pintype "passive"))
      (node (ref "RGB") (pin "VCC") (pinfunction "VCC_VCC") (pintype "passive"))
      (node (ref "R_LED1") (pin "1") (pinfunction "1_1") (pintype "passive"))
      (node (ref "R_LED2") (pin "1") (pinfunction "1_1") (pintype "passive"))
      (node (ref "U1") (pin "2") (pinfunction "VOUT_2") (pintype "passive"))
      (node (ref "U1") (pin "4") (pinfunction "VOUT_4") (pintype "passive"))
      (node (ref "U10") (pin "1") (pinfunction "VDD_IO_1") (pintype "passive"))
      (node (ref "U10") (pin "15") (pinfunction "RES_P15_VDD_15") (pintype "passive"))
      (node (ref "U10") (pin "16") (pinfunction "VDD_16") (pintype "passive"))
      (node (ref "U11") (pin "1") (pinfunction "VDD_IO_1") (pintype "passive"))
      (node (ref "U11") (pin "14") (pinfunction "VDD_14") (pintype "passive"))
      (node (ref "U2") (pin "1") (pinfunction "VBAT_1") (pintype "passive"))
      (node (ref "U2") (pin "13") (pinfunction "VDDA_13") (pintype "passive"))
      (node (ref "U2") (pin "19") (pinfunction "VDD_19") (pintype "passive"))
      (node (ref "U2") (pin "32") (pinfunction "VDD_32") (pintype "passive"))
      (node (ref "U2") (pin "48") (pinfunction "VDD_48") (pintype "passive"))
      (node (ref "U2") (pin "64") (pinfunction "VDD_64") (pintype "passive"))
      (node (ref "U3") (pin "4") (pinfunction "VDD_4") (pintype "passive"))
      (node (ref "U4") (pin "13") (pinfunction "VDD_13") (pintype "power_in"))
      (node (ref "U4") (pin "8") (pinfunction "VLOGC_8") (pintype "power_in"))
      (node (ref "U7") (pin "13") (pinfunction "VDDIO_13") (pintype "passive"))
      (node (ref "U7") (pin "2") (pinfunction "VDD_2") (pintype "passive"))
      (node (ref "U7") (pin "4") (pinfunction "S1_4") (pintype "passive"))
      (node (ref "U9") (pin "2") (pinfunction "VDD_2") (pintype "power_in"))
      (node (ref "U9") (pin "3") (pinfunction "VDDIO_3") (pintype "power_in"))
      (node (ref "UART") (pin "1") (pinfunction "1_1") (pintype "passive"))
    )
    (net (code "46") (name "5V") (class "Default")
      (node (ref "+5V") (pin "1") (pinfunction "1_1") (pintype "passive"))
      (node (ref "5V") (pin "1") (pinfunction "1_1") (pintype "passive"))
      (node (ref "BUZZER") (pin "1") (pinfunction "1_1") (pintype "passive"))
      (node (ref "C24") (pin "2") (pinfunction "2_2") (pintype "passive"))
      (node (ref "C8") (pin "A") (pinfunction "A_A") (pintype "passive"))
      (node (ref "D1") (pin "C") (pinfunction "2_C") (pintype "passive"))
      (node (ref "D2") (pin "C") (pinfunction "2_C") (pintype "passive"))
      (node (ref "D3") (pin "C") (pinfunction "2_C") (pintype "passive"))
      (node (ref "D4") (pin "C") (pinfunction "2_C") (pintype "passive"))
      (node (ref "D5") (pin "C") (pinfunction "2_C") (pintype "passive"))
      (node (ref "F1") (pin "1") (pinfunction "1_1") (pintype "passive"))
      (node (ref "Lights") (pin "2") (pinfunction "2_2") (pintype "passive"))
      (node (ref "PPM") (pin "1") (pinfunction "1_1") (pintype "passive"))
      (node (ref "U1") (pin "3") (pinfunction "VIN_3") (pintype "passive"))
      (node (ref "U6") (pin "1") (pinfunction "VIN_1") (pintype "passive"))
    )
    (net (code "47") (name "GND") (class "Default")
      (node (ref "B2") (pin "GND") (pinfunction "GND_GND") (pintype "passive"))
      (node (ref "BAT_SEN") (pin "3") (pinfunction "3_3") (pintype "passive"))
      (node (ref "BAT_SEN") (pin "4") (pinfunction "4_4") (pintype "passive"))
      (node (ref "C1") (pin "2") (pinfunction "2_2") (pintype "passive"))
      (node (ref "C10") (pin "1") (pinfunction "1_1") (pintype "passive"))
      (node (ref "C11") (pin "1") (pinfunction "1_1") (pintype "passive"))
      (node (ref "C12") (pin "C") (pinfunction "K_C") (pintype "passive"))
      (node (ref "C13") (pin "1") (pinfunction "1_1") (pintype "passive"))
      (node (ref "C14") (pin "2") (pinfunction "2_2") (pintype "passive"))
      (node (ref "C15") (pin "C") (pinfunction "K_C") (pintype "passive"))
      (node (ref "C16") (pin "2") (pinfunction "2_2") (pintype "passive"))
      (node (ref "C17") (pin "1") (pinfunction "1_1") (pintype "passive"))
      (node (ref "C18") (pin "1") (pinfunction "1_1") (pintype "passive"))
      (node (ref "C19") (pin "1") (pinfunction "1_1") (pintype "passive"))
      (node (ref "C2") (pin "2") (pinfunction "2_2") (pintype "passive"))
      (node (ref "C20") (pin "1") (pinfunction "1_1") (pintype "passive"))
      (node (ref "C22") (pin "1") (pinfunction "1_1") (pintype "passive"))
      (node (ref "C23") (pin "1") (pinfunction "1_1") (pintype "passive"))
      (node (ref "C24") (pin "1") (pinfunction "1_1") (pintype "passive"))
      (node (ref "C25") (pin "2") (pinfunction "2_2") (pintype "passive"))
      (node (ref "C26") (pin "1") (pinfunction "1_1") (pintype "passive"))
      (node (ref "C27") (pin "1") (pinfunction "1_1") (pintype "passive"))
      (node (ref "C28") (pin "1") (pinfunction "1_1") (pintype "passive"))
      (node (ref "C29") (pin "1") (pinfunction "1_1") (pintype "passive"))
      (node (ref "C3") (pin "1") (pinfunction "1_1") (pintype "passive"))
      (node (ref "C31") (pin "1") (pinfunction "1_1") (pintype "passive"))
      (node (ref "C4") (pin "1") (pinfunction "1_1") (pintype "passive"))
      (node (ref "C5") (pin "1") (pinfunction "1_1") (pintype "passive"))
      (node (ref "C6") (pin "2") (pinfunction "2_2") (pintype "passive"))
      (node (ref "C7") (pin "1") (pinfunction "1_1") (pintype "passive"))
      (node (ref "C8") (pin "C") (pinfunction "K_C") (pintype "passive"))
      (node (ref "C9") (pin "2") (pinfunction "2_2") (pintype "passive"))
      (node (ref "GND") (pin "1") (pinfunction "1_1") (pintype "passive"))
      (node (ref "JTAG") (pin "4") (pinfunction "4_4") (pintype "passive"))
      (node (ref "M1") (pin "1") (pinfunction "GND_1") (pintype "power_in"))
      (node (ref "P1") (pin "1") (pinfunction "1_1") (pintype "passive"))
      (node (ref "P1") (pin "10") (pinfunction "10_10") (pintype "passive"))
      (node (ref "P1") (pin "13") (pinfunction "13_13") (pintype "passive"))
      (node (ref "P1") (pin "4") (pinfunction "4_4") (pintype "passive"))
      (node (ref "P1") (pin "7") (pinfunction "7_7") (pintype "passive"))
      (node (ref "P2") (pin "1") (pinfunction "1_1") (pintype "passive"))
      (node (ref "P40") (pin "GND") (pinfunction "GND_GND") (pintype "passive"))
      (node (ref "PPM") (pin "3") (pinfunction "3_3") (pintype "passive"))
      (node (ref "PWR") (pin "C") (pinfunction "2_C") (pintype "passive"))
      (node (ref "Q1") (pin "1") (pinfunction "1_1") (pintype "passive"))
      (node (ref "Q2") (pin "1") (pinfunction "1_1") (pintype "passive"))
      (node (ref "R1") (pin "1") (pinfunction "1_1") (pintype "passive"))
      (node (ref "RESET") (pin "1") (pinfunction "1_1") (pintype "passive"))
      (node (ref "U1") (pin "1") (pinfunction "GND_1") (pintype "passive"))
      (node (ref "U10") (pin "10") (pinfunction "RES_P10_GND_10") (pintype "passive"))
      (node (ref "U10") (pin "11") (pinfunction "RES_P11_GND_11") (pintype "passive"))
      (node (ref "U10") (pin "12") (pinfunction "RES_P12_GND_12") (pintype "passive"))
      (node (ref "U10") (pin "13") (pinfunction "GND_13") (pintype "passive"))
      (node (ref "U10") (pin "8") (pinfunction "RES_P8_GND_8") (pintype "passive"))
      (node (ref "U10") (pin "9") (pinfunction "RES_P9_GND_9") (pintype "passive"))
      (node (ref "U11") (pin "10") (pinfunction "RSRV_10") (pintype "passive"))
      (node (ref "U11") (pin "12") (pinfunction "GND_12") (pintype "passive"))
      (node (ref "U11") (pin "13") (pinfunction "GND_13") (pintype "passive"))
      (node (ref "U11") (pin "16") (pinfunction "GND_16") (pintype "passive"))
      (node (ref "U11") (pin "5") (pinfunction "GND_5") (pintype "passive"))
      (node (ref "U2") (pin "12") (pinfunction "VSSA_12") (pintype "passive"))
      (node (ref "U2") (pin "18") (pinfunction "VSS_18") (pintype "passive"))
      (node (ref "U2") (pin "31") (pinfunction "VSS_31") (pintype "passive"))
      (node (ref "U2") (pin "47") (pinfunction "VSS_47") (pintype "passive"))
      (node (ref "U2") (pin "63") (pinfunction "VSS_63") (pintype "passive"))
      (node (ref "U3") (pin "2") (pinfunction "GND_2") (pintype "passive"))
      (node (ref "U4") (pin "1") (pinfunction "CLKIN_1") (pintype "input"))
      (node (ref "U4") (pin "11") (pinfunction "FSYNC_11") (pintype "passive"))
      (node (ref "U4") (pin "18") (pinfunction "GND_18") (pintype "power_in"))
      (node (ref "U4") (pin "25") (pinfunction "PAD_25") (pintype "power_in"))
      (node (ref "U4") (pin "9") (pinfunction "AD0_9") (pintype "input"))
      (node (ref "U5") (pin "10") (pinfunction "GND_10") (pintype "passive"))
      (node (ref "U5") (pin "12") (pinfunction "GND_12") (pintype "passive"))
      (node (ref "U5") (pin "13") (pinfunction "GND_13") (pintype "passive"))
      (node (ref "U5") (pin "24") (pinfunction "GND_24") (pintype "passive"))
      (node (ref "U6") (pin "2") (pinfunction "GND_2") (pintype "passive"))
      (node (ref "U7") (pin "11") (pinfunction "GND_11") (pintype "passive"))
      (node (ref "U7") (pin "17") (pinfunction "PAD_17") (pintype "passive"))
      (node (ref "U7") (pin "9") (pinfunction "GND_9") (pintype "passive"))
      (node (ref "U8") (pin "2") (pinfunction "GND_2") (pintype "passive"))
      (node (ref "U9") (pin "7") (pinfunction "GND_7") (pintype "power_in"))
      (node (ref "UART") (pin "4") (pinfunction "4_4") (pintype "passive"))
      (node (ref "USB") (pin "GND") (pinfunction "GND_GND") (pintype "power_in"))
    )
    (net (code "48") (name "Net-(D1-1)") (class "Default")
      (node (ref "BUZZER") (pin "2") (pinfunction "2_2") (pintype "passive"))
      (node (ref "D1") (pin "A") (pinfunction "1_A") (pintype "passive"))
      (node (ref "Q2") (pin "3") (pinfunction "3_3") (pintype "passive"))
    )
    (net (code "49") (name "Net-(D2-1)") (class "Default")
      (node (ref "D2") (pin "A") (pinfunction "1_A") (pintype "passive"))
      (node (ref "P1") (pin "2") (pinfunction "2_2") (pintype "passive"))
    )
    (net (code "50") (name "Net-(D3-1)") (class "Default")
      (node (ref "D3") (pin "A") (pinfunction "1_A") (pintype "passive"))
      (node (ref "P1") (pin "5") (pinfunction "5_5") (pintype "passive"))
    )
    (net (code "51") (name "Net-(D4-1)") (class "Default")
      (node (ref "D4") (pin "A") (pinfunction "1_A") (pintype "passive"))
      (node (ref "P1") (pin "8") (pinfunction "8_8") (pintype "passive"))
    )
    (net (code "52") (name "Net-(D5-1)") (class "Default")
      (node (ref "D5") (pin "A") (pinfunction "1_A") (pintype "passive"))
      (node (ref "P1") (pin "11") (pinfunction "11_11") (pintype "passive"))
      (node (ref "P1") (pin "14") (pinfunction "14_14") (pintype "passive"))
    )
    (net (code "53") (name "Net-(D6-2)") (class "Default")
      (node (ref "B2") (pin "VCC") (pinfunction "VCC_VCC") (pintype "passive"))
      (node (ref "D6") (pin "C") (pinfunction "2_C") (pintype "passive"))
      (node (ref "U5") (pin "22") (pinfunction "V_BCKP_22") (pintype "passive"))
    )
    (net (code "54") (name "Net-(F1-Pad2)") (class "Default")
      (node (ref "F1") (pin "2") (pinfunction "2_2") (pintype "passive"))
      (node (ref "USB") (pin "VBUS") (pinfunction "VBUS_VBUS") (pintype "power_in"))
    )
    (net (code "55") (name "Net-(GPS-1)") (class "Default")
      (node (ref "GPS") (pin "A") (pinfunction "1_A") (pintype "passive"))
      (node (ref "R27") (pin "1") (pinfunction "1_1") (pintype "passive"))
    )
    (net (code "56") (name "Net-(L1-Pad1)") (class "Default")
      (node (ref "L1") (pin "1") (pinfunction "1_1") (pintype "passive"))
      (node (ref "R26") (pin "2") (pinfunction "2_2") (pintype "passive"))
    )
    (net (code "57") (name "Net-(LED1-1)") (class "Default")
      (node (ref "LED1") (pin "A") (pinfunction "1_A") (pintype "passive"))
      (node (ref "R_LED1") (pin "2") (pinfunction "2_2") (pintype "passive"))
    )
    (net (code "58") (name "Net-(LED2-1)") (class "Default")
      (node (ref "LED2") (pin "A") (pinfunction "1_A") (pintype "passive"))
      (node (ref "R_LED2") (pin "2") (pinfunction "2_2") (pintype "passive"))
    )
    (net (code "59") (name "Net-(Lights-Pad1)") (class "Default")
      (node (ref "Lights") (pin "1") (pinfunction "1_1") (pintype "passive"))
      (node (ref "Q1") (pin "3") (pinfunction "3_3") (pintype "passive"))
    )
    (net (code "60") (name "Net-(P1-Pad3)") (class "Default")
      (node (ref "P1") (pin "3") (pinfunction "3_3") (pintype "passive"))
      (node (ref "R13") (pin "1") (pinfunction "1_1") (pintype "passive"))
    )
    (net (code "61") (name "Net-(P1-Pad6)") (class "Default")
      (node (ref "P1") (pin "6") (pinfunction "6_6") (pintype "passive"))
      (node (ref "R14") (pin "1") (pinfunction "1_1") (pintype "passive"))
    )
    (net (code "62") (name "Net-(P1-Pad9)") (class "Default")
      (node (ref "P1") (pin "9") (pinfunction "9_9") (pintype "passive"))
      (node (ref "R15") (pin "1") (pinfunction "1_1") (pintype "passive"))
    )
    (net (code "63") (name "Net-(P1-Pad12)") (class "Default")
      (node (ref "P1") (pin "12") (pinfunction "12_12") (pintype "passive"))
      (node (ref "R16") (pin "1") (pinfunction "1_1") (pintype "passive"))
    )
    (net (code "64") (name "Net-(P1-Pad15)") (class "Default")
      (node (ref "P1") (pin "15") (pinfunction "15_15") (pintype "passive"))
      (node (ref "R17") (pin "1") (pinfunction "1_1") (pintype "passive"))
    )
    (net (code "65") (name "Net-(PC13-Pad1)") (class "Default")
      (node (ref "PC13") (pin "1") (pinfunction "1_1") (pintype "passive"))
      (node (ref "R7") (pin "2") (pinfunction "2_2") (pintype "passive"))
    )
    (net (code "66") (name "Net-(PD1-Pad1)") (class "Default")
      (node (ref "PD1") (pin "1") (pinfunction "1_1") (pintype "passive"))
      (node (ref "R8") (pin "2") (pinfunction "2_2") (pintype "passive"))
    )
    (net (code "67") (name "Net-(PPM-Pad2)") (class "Default")
      (node (ref "PPM") (pin "2") (pinfunction "2_2") (pintype "passive"))
      (node (ref "R32") (pin "2") (pinfunction "2_2") (pintype "passive"))
    )
    (net (code "68") (name "Net-(PWR-1)") (class "Default")
      (node (ref "PWR") (pin "A") (pinfunction "1_A") (pintype "passive"))
      (node (ref "R9") (pin "2") (pinfunction "2_2") (pintype "passive"))
    )
    (net (code "69") (name "Net-(Q1-Pad2)") (class "Default")
      (node (ref "Q1") (pin "2") (pinfunction "2_2") (pintype "passive"))
      (node (ref "R3") (pin "2") (pinfunction "2_2") (pintype "passive"))
    )
    (net (code "70") (name "Net-(Q2-Pad2)") (class "Default")
      (node (ref "Q2") (pin "2") (pinfunction "2_2") (pintype "passive"))
      (node (ref "R12") (pin "1") (pinfunction "1_1") (pintype "passive"))
    )
    (net (code "71") (name "Net-(R11-Pad1)") (class "Default")
      (node (ref "R11") (pin "1") (pinfunction "1_1") (pintype "passive"))
      (node (ref "UART") (pin "2") (pinfunction "2_2") (pintype "passive"))
    )
    (net (code "72") (name "Net-(R19-Pad1)") (class "Default")
      (node (ref "R19") (pin "1") (pinfunction "1_1") (pintype "passive"))
      (node (ref "UART") (pin "3") (pinfunction "3_3") (pintype "passive"))
    )
    (net (code "73") (name "Net-(RGB-PadB)") (class "Default")
      (node (ref "RGB") (pin "B") (pinfunction "B_B") (pintype "passive"))
      (node (ref "R_B") (pin "1") (pinfunction "1_1") (pintype "passive"))
    )
    (net (code "74") (name "Net-(RGB-PadG)") (class "Default")
      (node (ref "RGB") (pin "G") (pinfunction "G_G") (pintype "passive"))
      (node (ref "R_G") (pin "1") (pinfunction "1_1") (pintype "passive"))
    )
    (net (code "75") (name "Net-(RGB-PadR)") (class "Default")
      (node (ref "RGB") (pin "R") (pinfunction "R_R") (pintype "passive"))
      (node (ref "R_R") (pin "1") (pinfunction "1_1") (pintype "passive"))
    )
    (net (code "76") (name "Net-(U2-BOOT0)") (class "Default")
      (node (ref "R1") (pin "2") (pinfunction "2_2") (pintype "passive"))
      (node (ref "U2") (pin "60") (pinfunction "BOOT0_60") (pintype "passive"))
    )
    (net (code "77") (name "Net-(U2-PB2{slash}BOOT1)") (class "Default")
      (node (ref "PB2") (pin "1") (pinfunction "1_1") (pintype "passive"))
      (node (ref "U2") (pin "28") (pinfunction "PB2/BOOT1_28") (pintype "passive"))
    )
    (net (code "78") (name "Net-(U2-PB14{slash}SPI2_MISO{slash}TIM1_CH2N)") (class "Default")
      (node (ref "PB14") (pin "1") (pinfunction "1_1") (pintype "passive"))
      (node (ref "U2") (pin "35") (pinfunction "PB14/SPI2_MISO/TIM1_CH2N_35") (pintype "passive"))
    )
    (net (code "79") (name "Net-(U2-PD2{slash}TIM3_ETR{slash}U5_RX{slash}SDIO_CMD)") (class "Default")
      (node (ref "PD2") (pin "1") (pinfunction "1_1") (pintype "passive"))
      (node (ref "U2") (pin "54") (pinfunction "PD2/TIM3_ETR/U5_RX/SDIO_CMD_54") (pintype "passive"))
    )
    (net (code "80") (name "Net-(U4-CPOUT)") (class "Default")
      (node (ref "C14") (pin "1") (pinfunction "1_1") (pintype "passive"))
      (node (ref "U4") (pin "20") (pinfunction "CPOUT_20") (pintype "passive"))
    )
    (net (code "81") (name "Net-(U4-REGOUT)") (class "Default")
      (node (ref "C16") (pin "1") (pinfunction "1_1") (pintype "passive"))
      (node (ref "U4") (pin "10") (pinfunction "REGOUT_10") (pintype "passive"))
    )
    (net (code "82") (name "Net-(U5-RF_IN)") (class "Default")
      (node (ref "L1") (pin "2") (pinfunction "2_2") (pintype "passive"))
      (node (ref "P40") (pin "ANT") (pinfunction "ANT_ANT") (pintype "passive"))
      (node (ref "U5") (pin "11") (pinfunction "RF_IN_11") (pintype "passive"))
    )
    (net (code "83") (name "Net-(U5-RX)") (class "Default")
      (node (ref "R5") (pin "2") (pinfunction "2_2") (pintype "passive"))
      (node (ref "U5") (pin "21") (pinfunction "RX_21") (pintype "passive"))
    )
    (net (code "84") (name "Net-(U5-TX)") (class "Default")
      (node (ref "R2") (pin "2") (pinfunction "2_2") (pintype "passive"))
      (node (ref "U5") (pin "20") (pinfunction "TX_20") (pintype "passive"))
    )
    (net (code "85") (name "Net-(U5-VCC_RF)") (class "Default")
      (node (ref "R26") (pin "1") (pinfunction "1_1") (pintype "passive"))
      (node (ref "U5") (pin "8") (pinfunction "NC_8") (pintype "passive"))
      (node (ref "U5") (pin "9") (pinfunction "VCC_RF_9") (pintype "passive"))
    )
    (net (code "86") (name "Net-(U6-BP)") (class "Default")
      (node (ref "C9") (pin "1") (pinfunction "1_1") (pintype "passive"))
      (node (ref "U6") (pin "4") (pinfunction "BP_4") (pintype "passive"))
    )
    (net (code "87") (name "Net-(U7-C1)") (class "Default")
      (node (ref "C19") (pin "2") (pinfunction "2_2") (pintype "passive"))
      (node (ref "U7") (pin "10") (pinfunction "C1_10") (pintype "passive"))
    )
    (net (code "88") (name "Net-(U7-SETC)") (class "Default")
      (node (ref "C21") (pin "2") (pinfunction "2_2") (pintype "passive"))
      (node (ref "U7") (pin "12") (pinfunction "SETC_12") (pintype "passive"))
    )
    (net (code "89") (name "Net-(U7-SETP)") (class "Default")
      (node (ref "C21") (pin "1") (pinfunction "1_1") (pintype "passive"))
      (node (ref "U7") (pin "8") (pinfunction "SETP_8") (pintype "passive"))
    )
    (net (code "90") (name "Net-(U8-D1)") (class "Default")
      (node (ref "R24") (pin "1") (pinfunction "1_1") (pintype "passive"))
      (node (ref "U8") (pin "1") (pinfunction "D1_1") (pintype "passive"))
      (node (ref "USB") (pin "D-") (pinfunction "D-_D-") (pintype "bidirectional"))
    )
    (net (code "91") (name "Net-(U8-D2)") (class "Default")
      (node (ref "R25") (pin "1") (pinfunction "1_1") (pintype "passive"))
      (node (ref "U8") (pin "3") (pinfunction "D2_3") (pintype "passive"))
      (node (ref "USB") (pin "D+") (pinfunction "D+_D+") (pintype "bidirectional"))
    )
    (net (code "92") (name "Net-(U8-D3)") (class "Default")
      (node (ref "JTAG") (pin "2") (pinfunction "2_2") (pintype "passive"))
      (node (ref "R22") (pin "1") (pinfunction "1_1") (pintype "passive"))
      (node (ref "U8") (pin "4") (pinfunction "D3_4") (pintype "passive"))
    )
    (net (code "93") (name "Net-(U8-D4)") (class "Default")
      (node (ref "JTAG") (pin "3") (pinfunction "3_3") (pintype "passive"))
      (node (ref "R23") (pin "1") (pinfunction "1_1") (pintype "passive"))
      (node (ref "U8") (pin "5") (pinfunction "D4_5") (pintype "passive"))
    )
    (net (code "94") (name "Net-(U10-PLLFILT)") (class "Default")
      (node (ref "C28") (pin "2") (pinfunction "2_2") (pintype "passive"))
      (node (ref "U10") (pin "14") (pinfunction "PLLFILT_14") (pintype "passive"))
    )
    (net (code "95") (name "Net-(U11-C1)") (class "Default")
      (node (ref "C31") (pin "2") (pinfunction "2_2") (pintype "passive"))
      (node (ref "U11") (pin "15") (pinfunction "C1_15") (pintype "passive"))
    )
    (net (code "96") (name "Net-(U11-SETC)") (class "Default")
      (node (ref "C30") (pin "2") (pinfunction "2_2") (pintype "passive"))
      (node (ref "U11") (pin "2") (pinfunction "SETC_2") (pintype "passive"))
    )
    (net (code "97") (name "Net-(U11-SETP)") (class "Default")
      (node (ref "C30") (pin "1") (pinfunction "1_1") (pintype "passive"))
      (node (ref "U11") (pin "3") (pinfunction "SETP_3") (pintype "passive"))
    )
    (net (code "98") (name "unconnected-(U2-PA5{slash}SPI1_SCK{slash}ADC5{slash}DAC2-Pad21)") (class "Default")
      (node (ref "U2") (pin "21") (pinfunction "PA5/SPI1_SCK/ADC5/DAC2_21") (pintype "passive"))
    )
    (net (code "99") (name "unconnected-(U2-PA6{slash}SPI1_MISO{slash}ADC6{slash}TIM3_CH1{slash}TIM8_BKIN-Pad22)") (class "Default")
      (node (ref "U2") (pin "22") (pinfunction "PA6/SPI1_MISO/ADC6/TIM3_CH1/TIM8_BKIN_22") (pintype "passive"))
    )
    (net (code "100") (name "unconnected-(U2-PA7{slash}SPI1_MOSI{slash}ADC7{slash}TIM3_CH2{slash}TIM8_CH1N-Pad23)") (class "Default")
      (node (ref "U2") (pin "23") (pinfunction "PA7/SPI1_MOSI/ADC7/TIM3_CH2/TIM8_CH1N_23") (pintype "passive"))
    )
    (net (code "101") (name "unconnected-(U2-PA15{slash}JTDI{slash}SPI3_NSS{slash}I2S3_WS-Pad50)") (class "Default")
      (node (ref "U2") (pin "50") (pinfunction "PA15/JTDI/SPI3_NSS/I2S3_WS_50") (pintype "passive"))
    )
    (net (code "102") (name "unconnected-(U2-PC1{slash}ADC11-Pad9)") (class "Default")
      (node (ref "U2") (pin "9") (pinfunction "PC1/ADC11_9") (pintype "passive"))
    )
    (net (code "103") (name "unconnected-(U2-PC6{slash}I2S2_MCK{slash}TIM8_CH1{slash}SDIO_D6-Pad37)") (class "Default")
      (node (ref "U2") (pin "37") (pinfunction "PC6/I2S2_MCK/TIM8_CH1/SDIO_D6_37") (pintype "passive"))
    )
    (net (code "104") (name "unconnected-(U2-PC9{slash}TIM8_CH4{slash}SDIO_D1-Pad40)") (class "Default")
      (node (ref "U2") (pin "40") (pinfunction "PC9/TIM8_CH4/SDIO_D1_40") (pintype "passive"))
    )
    (net (code "105") (name "unconnected-(U3-NC-Pad1)") (class "Default")
      (node (ref "U3") (pin "1") (pinfunction "NC_1") (pintype "passive"))
    )
    (net (code "106") (name "unconnected-(U4-CLKOUT-Pad22)") (class "Default")
      (node (ref "U4") (pin "22") (pinfunction "CLKOUT_22") (pintype "output"))
    )
    (net (code "107") (name "unconnected-(U4-FESV-Pad19)") (class "Default")
      (node (ref "U4") (pin "19") (pinfunction "FESV_19") (pintype "passive"))
    )
    (net (code "108") (name "unconnected-(U4-NC-Pad2)") (class "Default")
      (node (ref "U4") (pin "2") (pinfunction "NC_2") (pintype "passive"))
    )
    (net (code "109") (name "unconnected-(U4-NC-Pad3)") (class "Default")
      (node (ref "U4") (pin "3") (pinfunction "NC_3") (pintype "passive"))
    )
    (net (code "110") (name "unconnected-(U4-NC-Pad4)") (class "Default")
      (node (ref "U4") (pin "4") (pinfunction "NC_4") (pintype "passive"))
    )
    (net (code "111") (name "unconnected-(U4-NC-Pad5)") (class "Default")
      (node (ref "U4") (pin "5") (pinfunction "NC_5") (pintype "passive"))
    )
    (net (code "112") (name "unconnected-(U4-NC-Pad14)") (class "Default")
      (node (ref "U4") (pin "14") (pinfunction "NC_14") (pintype "passive"))
    )
    (net (code "113") (name "unconnected-(U4-NC-Pad15)") (class "Default")
      (node (ref "U4") (pin "15") (pinfunction "NC_15") (pintype "passive"))
    )
    (net (code "114") (name "unconnected-(U4-NC-Pad16)") (class "Default")
      (node (ref "U4") (pin "16") (pinfunction "NC_16") (pintype "passive"))
    )
    (net (code "115") (name "unconnected-(U4-NC-Pad17)") (class "Default")
      (node (ref "U4") (pin "17") (pinfunction "NC_17") (pintype "passive"))
    )
    (net (code "116") (name "unconnected-(U4-RESV-Pad21)") (class "Default")
      (node (ref "U4") (pin "21") (pinfunction "RESV_21") (pintype "passive"))
    )
    (net (code "117") (name "unconnected-(U4-XCL-Pad7)") (class "Default")
      (node (ref "U4") (pin "7") (pinfunction "XCL_7") (pintype "passive"))
    )
    (net (code "118") (name "unconnected-(U4-XDA-Pad6)") (class "Default")
      (node (ref "U4") (pin "6") (pinfunction "XDA_6") (pintype "passive"))
    )
    (net (code "119") (name "unconnected-(U5-CFG_GPS0{slash}SCK-Pad16)") (class "Default")
      (node (ref "U5") (pin "16") (pinfunction "CFG_GPS0/SCK_16") (pintype "passive"))
    )
    (net (code "120") (name "unconnected-(U5-EXTINT0-Pad4)") (class "Default")
      (node (ref "U5") (pin "4") (pinfunction "EXTINT0_4") (pintype "passive"))
    )
    (net (code "121") (name "unconnected-(U5-MISO{slash}CFG_COM1-Pad15)") (class "Default")
      (node (ref "U5") (pin "15") (pinfunction "MISO/CFG_COM1_15") (pintype "passive"))
    )
    (net (code "122") (name "unconnected-(U5-MOSI{slash}CFG_COM0-Pad14)") (class "Default")
      (node (ref "U5") (pin "14") (pinfunction "MOSI/CFG_COM0_14") (pintype "passive"))
    )
    (net (code "123") (name "unconnected-(U5-NC-Pad1)") (class "Default")
      (node (ref "U5") (pin "1") (pinfunction "NC_1") (pintype "passive"))
    )
    (net (code "124") (name "unconnected-(U5-NC-Pad17)") (class "Default")
      (node (ref "U5") (pin "17") (pinfunction "NC_17") (pintype "passive"))
    )
    (net (code "125") (name "unconnected-(U5-SCL2-Pad19)") (class "Default")
      (node (ref "U5") (pin "19") (pinfunction "SCL2_19") (pintype "passive"))
    )
    (net (code "126") (name "unconnected-(U5-SDA2-Pad18)") (class "Default")
      (node (ref "U5") (pin "18") (pinfunction "SDA2_18") (pintype "passive"))
    )
    (net (code "127") (name "unconnected-(U5-SS_N-Pad2)") (class "Default")
      (node (ref "U5") (pin "2") (pinfunction "SS_N_2") (pintype "passive"))
    )
    (net (code "128") (name "unconnected-(U5-USB_DM-Pad5)") (class "Default")
      (node (ref "U5") (pin "5") (pinfunction "USB_DM_5") (pintype "passive"))
    )
    (net (code "129") (name "unconnected-(U5-USB_DP-Pad6)") (class "Default")
      (node (ref "U5") (pin "6") (pinfunction "USB_DP_6") (pintype "passive"))
    )
    (net (code "130") (name "unconnected-(U7-DRDY-Pad15)") (class "Default")
      (node (ref "U7") (pin "15") (pinfunction "DRDY_15") (pintype "passive"))
    )
    (net (code "131") (name "unconnected-(U7-NC-Pad3)") (class "Default")
      (node (ref "U7") (pin "3") (pinfunction "NC_3") (pintype "passive"))
    )
    (net (code "132") (name "unconnected-(U7-NC-Pad5)") (class "Default")
      (node (ref "U7") (pin "5") (pinfunction "NC_5") (pintype "passive"))
    )
    (net (code "133") (name "unconnected-(U7-NC-Pad6)") (class "Default")
      (node (ref "U7") (pin "6") (pinfunction "NC_6") (pintype "passive"))
    )
    (net (code "134") (name "unconnected-(U7-NC-Pad7)") (class "Default")
      (node (ref "U7") (pin "7") (pinfunction "NC_7") (pintype "passive"))
    )
    (net (code "135") (name "unconnected-(U7-NC-Pad14)") (class "Default")
      (node (ref "U7") (pin "14") (pinfunction "NC_14") (pintype "passive"))
    )
    (net (code "136") (name "unconnected-(U9-CS-Pad1)") (class "Default")
      (node (ref "U9") (pin "1") (pinfunction "CS_1") (pintype "input+no_connect"))
    )
    (net (code "137") (name "unconnected-(U9-SDO-Pad4)") (class "Default")
      (node (ref "U9") (pin "4") (pinfunction "SDO_4") (pintype "output+no_connect"))
    )
    (net (code "138") (name "unconnected-(U10-INT1-Pad7)") (class "Default")
      (node (ref "U10") (pin "7") (pinfunction "INT1_7") (pintype "output"))
    )
    (net (code "139") (name "unconnected-(USB-PadID)") (class "Default")
      (node (ref "USB") (pin "ID") (pinfunction "ID_ID") (pintype "passive"))
    )
  )
)
